# MB1297_USB_OTG_FS.net
KiCad netlist of a schematic drawn in Altium Designer
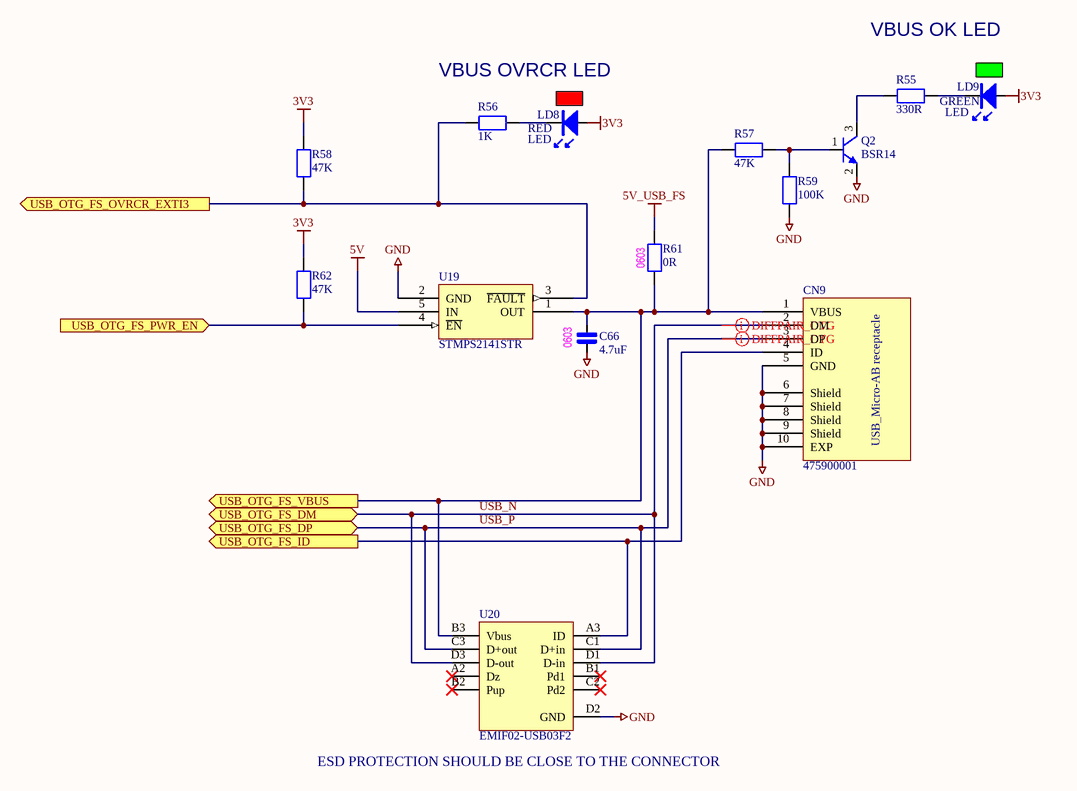
[diagram p0: MB1297_USB_OTG_FS.SchDoc]

(export (version "E")
  (design (tool "Eeschema 10.0.6"))
  (components
    (comp (ref "C66")
      (value "4.7uF")
      (footprint "0603_CAP_NPOL")
      (description "Capacitor_not polarized")
      (libsource (lib "ST_Lib3D") (part "CAP_NPOL"))
    )
    (comp (ref "CN9")
      (value "475900001")
      (footprint "CON_USBMICROAB_MOLEX_47590-0001_H3")
      (description "USB-MICRO-AB, 47590-0001, SMT, MOLEX")
      (libsource (lib "MCD_TEMP_PCH") (part "475900001"))
    )
    (comp (ref "LD8")
      (value "LED")
      (footprint "0603_LED_RED")
      (description "Light-Emitting Diode")
      (fields (field (name "COLOR") "RED"))
      (libsource (lib "ST_Lib3D") (part "LED"))
    )
    (comp (ref "LD9")
      (value "LED")
      (footprint "0603_LED_GREEN")
      (description "Light-Emitting Diode")
      (fields (field (name "COLOR") "GREEN"))
      (libsource (lib "ST_Lib3D") (part "LED"))
    )
    (comp (ref "Q2")
      (value "BSR14")
      (footprint "ST_Lib3D:SOT23-3")
      (description "BSR14 NPN switching transistor SOT23 (Marking U8)")
      (libsource (lib "ST_Lib3D") (part "BSR14"))
    )
    (comp (ref "R55")
      (value "330R")
      (footprint "0402")
      (description "Resistor")
      (libsource (lib "Lib3D_Altium10_Schlib") (part "RES"))
    )
    (comp (ref "R56")
      (value "1K")
      (footprint "0402")
      (description "Resistor")
      (libsource (lib "Lib3D_Altium10_Schlib") (part "RES"))
    )
    (comp (ref "R57")
      (value "47K")
      (footprint "0402")
      (description "Resistor")
      (libsource (lib "Lib3D_Altium10_Schlib") (part "RES"))
    )
    (comp (ref "R58")
      (value "47K")
      (footprint "0402")
      (description "Resistor")
      (libsource (lib "Lib3D_Altium10_Schlib") (part "RES"))
    )
    (comp (ref "R59")
      (value "100K")
      (footprint "0402")
      (description "Resistor")
      (libsource (lib "Lib3D_Altium10_Schlib") (part "RES"))
    )
    (comp (ref "R61")
      (value "0R")
      (footprint "0603_RES")
      (description "Resistor")
      (libsource (lib "Lib3D_Altium10_Schlib") (part "RES"))
    )
    (comp (ref "R62")
      (value "47K")
      (footprint "0402")
      (description "Resistor")
      (libsource (lib "Lib3D_Altium10_Schlib") (part "RES"))
    )
    (comp (ref "U19")
      (value "STMPS2141STR")
      (footprint "MOS_SOT23-5L")
      (description "Enhanced single channel power switches")
      (libsource (lib "MCD_TEMP_PCH") (part "STMPS2141STR"))
    )
    (comp (ref "U20")
      (value "EMIF02-USB03F2")
      (footprint "ESD_FLIP-CHIP-BGA11_1P44X1P94_P050")
      (description "2-line IPAD, EMI filter including ESD protection")
      (libsource (lib "MCD_TEMP_PCH") (part "EMIF02-USB03F2"))
    )
  )
  (nets
    (net (code "1") (name "/USB_N") (class "Default")
      (node (ref "CN9") (pin "2") (pinfunction "DM_2") (pintype "passive"))
      (node (ref "U20") (pin "D1") (pinfunction "D-in_D1") (pintype "passive"))
      (node (ref "U20") (pin "D3") (pinfunction "D-out_D3") (pintype "passive"))
    )
    (net (code "2") (name "/USB_OTG_FS_ID") (class "Default")
      (node (ref "CN9") (pin "4") (pinfunction "ID_4") (pintype "passive"))
      (node (ref "U20") (pin "A3") (pinfunction "ID_A3") (pintype "passive"))
    )
    (net (code "3") (name "/USB_OTG_FS_OVRCR_EXTI3") (class "Default")
      (node (ref "R56") (pin "1") (pinfunction "1_1") (pintype "passive"))
      (node (ref "R58") (pin "2") (pinfunction "2_2") (pintype "passive"))
      (node (ref "U19") (pin "3") (pinfunction "~{FAULT}_3") (pintype "output"))
    )
    (net (code "4") (name "/USB_OTG_FS_PWR_EN") (class "Default")
      (node (ref "R62") (pin "2") (pinfunction "2_2") (pintype "passive"))
      (node (ref "U19") (pin "4") (pinfunction "~{EN}_4") (pintype "input"))
    )
    (net (code "5") (name "/USB_OTG_FS_VBUS") (class "Default")
      (node (ref "C66") (pin "1") (pinfunction "1_1") (pintype "passive"))
      (node (ref "CN9") (pin "1") (pinfunction "VBUS_1") (pintype "passive"))
      (node (ref "R57") (pin "1") (pinfunction "1_1") (pintype "passive"))
      (node (ref "R61") (pin "2") (pinfunction "2_2") (pintype "passive"))
      (node (ref "U19") (pin "1") (pinfunction "OUT_1") (pintype "passive"))
      (node (ref "U20") (pin "B3") (pinfunction "Vbus_B3") (pintype "passive"))
    )
    (net (code "6") (name "/USB_P") (class "Default")
      (node (ref "CN9") (pin "3") (pinfunction "DP_3") (pintype "passive"))
      (node (ref "U20") (pin "C1") (pinfunction "D+in_C1") (pintype "passive"))
      (node (ref "U20") (pin "C3") (pinfunction "D+out_C3") (pintype "passive"))
    )
    (net (code "7") (name "3V3") (class "Default")
      (node (ref "LD8") (pin "A") (pinfunction "A_A") (pintype "passive"))
      (node (ref "LD9") (pin "A") (pinfunction "A_A") (pintype "passive"))
      (node (ref "R58") (pin "1") (pinfunction "1_1") (pintype "passive"))
      (node (ref "R62") (pin "1") (pinfunction "1_1") (pintype "passive"))
    )
    (net (code "8") (name "5V") (class "Default")
      (node (ref "U19") (pin "5") (pinfunction "IN_5") (pintype "passive"))
    )
    (net (code "9") (name "5V_USB_FS") (class "Default")
      (node (ref "R61") (pin "1") (pinfunction "1_1") (pintype "passive"))
    )
    (net (code "10") (name "GND") (class "Default")
      (node (ref "C66") (pin "2") (pinfunction "2_2") (pintype "passive"))
      (node (ref "CN9") (pin "10") (pinfunction "EXP_10") (pintype "passive"))
      (node (ref "CN9") (pin "5") (pinfunction "GND_5") (pintype "passive"))
      (node (ref "CN9") (pin "6") (pinfunction "Shield_6") (pintype "passive"))
      (node (ref "CN9") (pin "7") (pinfunction "Shield_7") (pintype "passive"))
      (node (ref "CN9") (pin "8") (pinfunction "Shield_8") (pintype "passive"))
      (node (ref "CN9") (pin "9") (pinfunction "Shield_9") (pintype "passive"))
      (node (ref "Q2") (pin "2") (pinfunction "E_2") (pintype "passive"))
      (node (ref "R59") (pin "1") (pinfunction "1_1") (pintype "passive"))
      (node (ref "U19") (pin "2") (pinfunction "GND_2") (pintype "passive"))
      (node (ref "U20") (pin "D2") (pinfunction "GND_D2") (pintype "passive"))
    )
    (net (code "11") (name "Net-(LD8-PadK)") (class "Default")
      (node (ref "LD8") (pin "K") (pinfunction "K_K") (pintype "passive"))
      (node (ref "R56") (pin "2") (pinfunction "2_2") (pintype "passive"))
    )
    (net (code "12") (name "Net-(LD9-PadK)") (class "Default")
      (node (ref "LD9") (pin "K") (pinfunction "K_K") (pintype "passive"))
      (node (ref "R55") (pin "2") (pinfunction "2_2") (pintype "passive"))
    )
    (net (code "13") (name "Net-(Q2-B)") (class "Default")
      (node (ref "Q2") (pin "1") (pinfunction "B_1") (pintype "passive"))
      (node (ref "R57") (pin "2") (pinfunction "2_2") (pintype "passive"))
      (node (ref "R59") (pin "2") (pinfunction "2_2") (pintype "passive"))
    )
    (net (code "14") (name "Net-(Q2-C)") (class "Default")
      (node (ref "Q2") (pin "3") (pinfunction "C_3") (pintype "passive"))
      (node (ref "R55") (pin "1") (pinfunction "1_1") (pintype "passive"))
    )
    (net (code "15") (name "unconnected-(U20-Dz-PadA2)") (class "Default")
      (node (ref "U20") (pin "A2") (pinfunction "Dz_A2") (pintype "passive+no_connect"))
    )
    (net (code "16") (name "unconnected-(U20-Pd1-PadB1)") (class "Default")
      (node (ref "U20") (pin "B1") (pinfunction "Pd1_B1") (pintype "passive+no_connect"))
    )
    (net (code "17") (name "unconnected-(U20-Pd2-PadC2)") (class "Default")
      (node (ref "U20") (pin "C2") (pinfunction "Pd2_C2") (pintype "passive+no_connect"))
    )
    (net (code "18") (name "unconnected-(U20-Pup-PadB2)") (class "Default")
      (node (ref "U20") (pin "B2") (pinfunction "Pup_B2") (pintype "passive+no_connect"))
    )
  )
)
